# SLAMStruderBrd.net
KiCad netlist of a schematic drawn in EAGLE
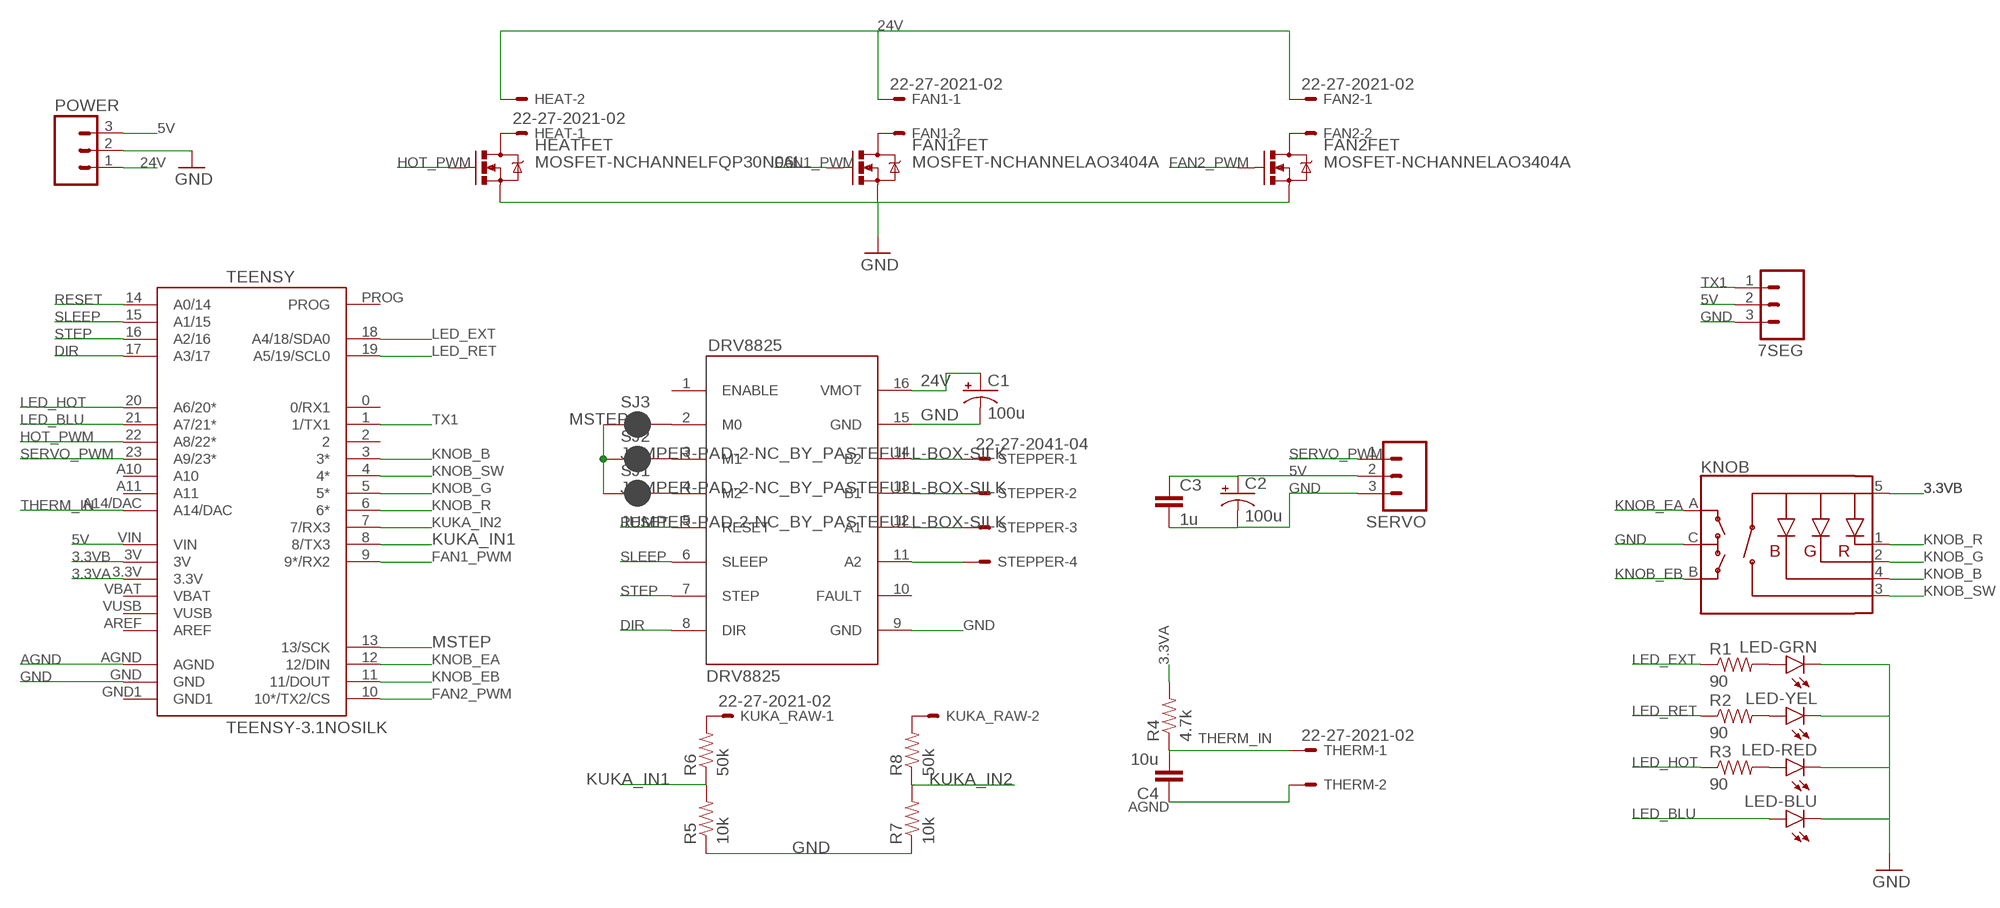
[diagram p0: schematic, sheet 1]

(export (version "E")
  (design (tool "Eeschema 10.0.6"))
  (components
    (comp (ref "7SEG")
      (value "M031X03_NO_SILK")
      (footprint "eagle-import:1X03_NO_SILK")
      (libsource (lib "eagle-import") (part "M031X03_NO_SILK"))
    )
    (comp (ref "C1")
      (value "100u")
      (footprint "eagle-import:PANASONIC_E")
      (libsource (lib "eagle-import") (part "CAP_POLE"))
    )
    (comp (ref "C2")
      (value "100u")
      (footprint "eagle-import:PANASONIC_E")
      (libsource (lib "eagle-import") (part "CAP_POLE"))
    )
    (comp (ref "C3")
      (value "1u")
      (footprint "eagle-import:0805")
      (libsource (lib "eagle-import") (part "CAP0805"))
    )
    (comp (ref "C4")
      (value "10u")
      (footprint "eagle-import:0805")
      (libsource (lib "eagle-import") (part "CAP0805"))
    )
    (comp (ref "DRV8825")
      (value "DRV8825")
      (footprint "eagle-import:STEPPER_DRIVER")
      (libsource (lib "eagle-import") (part "DRV8825"))
    )
    (comp (ref "FAN1")
      (value "22-27-2021-02")
      (footprint "eagle-import:6410-02")
      (libsource (lib "eagle-import") (part "22-?-0227-2021"))
    )
    (comp (ref "FAN1FET")
      (value "MOSFET-NCHANNELAO3404A")
      (footprint "eagle-import:SOT23-3")
      (libsource (lib "eagle-import") (part "MOSFET-NCHANNELAO3404A"))
    )
    (comp (ref "FAN2")
      (value "22-27-2021-02")
      (footprint "eagle-import:6410-02")
      (libsource (lib "eagle-import") (part "22-?-0227-2021"))
    )
    (comp (ref "FAN2FET")
      (value "MOSFET-NCHANNELAO3404A")
      (footprint "eagle-import:SOT23-3")
      (libsource (lib "eagle-import") (part "MOSFET-NCHANNELAO3404A"))
    )
    (comp (ref "HEAT")
      (value "22-27-2021-02")
      (footprint "eagle-import:6410-02")
      (libsource (lib "eagle-import") (part "22-?-0227-2021"))
    )
    (comp (ref "HEATFET")
      (value "MOSFET-NCHANNELFQP30N06L")
      (footprint "eagle-import:TO220V")
      (libsource (lib "eagle-import") (part "MOSFET-NCHANNELFQP30N06L"))
    )
    (comp (ref "KNOB")
      (value "ENCODER_RGB_CA")
      (footprint "eagle-import:ENCODER_LED_3")
      (libsource (lib "eagle-import") (part "ENCODER_RGB_CA"))
    )
    (comp (ref "KUKA_RAW")
      (value "22-27-2021-02")
      (footprint "eagle-import:6410-02")
      (libsource (lib "eagle-import") (part "22-?-0227-2021"))
    )
    (comp (ref "LED-BLU")
      (value "LED5MM")
      (footprint "eagle-import:LED5MM")
      (libsource (lib "eagle-import") (part "LED5MM"))
    )
    (comp (ref "LED-GRN")
      (value "LED5MM")
      (footprint "eagle-import:LED5MM")
      (libsource (lib "eagle-import") (part "LED5MM"))
    )
    (comp (ref "LED-RED")
      (value "LED5MM")
      (footprint "eagle-import:LED5MM")
      (libsource (lib "eagle-import") (part "LED5MM"))
    )
    (comp (ref "LED-YEL")
      (value "LED5MM")
      (footprint "eagle-import:LED5MM")
      (libsource (lib "eagle-import") (part "LED5MM"))
    )
    (comp (ref "POWER")
      (value "M03SCREW")
      (footprint "eagle-import:SCREWTERMINAL-3.5MM-3")
      (libsource (lib "eagle-import") (part "M03SCREW"))
    )
    (comp (ref "R1")
      (value "90")
      (footprint "eagle-import:0805")
      (libsource (lib "eagle-import") (part "RESISTOR0805-RES"))
    )
    (comp (ref "R2")
      (value "90")
      (footprint "eagle-import:0805")
      (libsource (lib "eagle-import") (part "RESISTOR0805-RES"))
    )
    (comp (ref "R3")
      (value "90")
      (footprint "eagle-import:0805")
      (libsource (lib "eagle-import") (part "RESISTOR0805-RES"))
    )
    (comp (ref "R4")
      (value "4.7k")
      (footprint "eagle-import:0805")
      (libsource (lib "eagle-import") (part "RESISTOR0805-RES"))
    )
    (comp (ref "R5")
      (value "10k")
      (footprint "eagle-import:0805")
      (libsource (lib "eagle-import") (part "RESISTOR0805-RES"))
    )
    (comp (ref "R6")
      (value "50k")
      (footprint "eagle-import:0805")
      (libsource (lib "eagle-import") (part "RESISTOR0805-RES"))
    )
    (comp (ref "R7")
      (value "10k")
      (footprint "eagle-import:0805")
      (libsource (lib "eagle-import") (part "RESISTOR0805-RES"))
    )
    (comp (ref "R8")
      (value "50k")
      (footprint "eagle-import:0805")
      (libsource (lib "eagle-import") (part "RESISTOR0805-RES"))
    )
    (comp (ref "SERVO")
      (value "M03PTH")
      (footprint "eagle-import:1X03")
      (libsource (lib "eagle-import") (part "M03PTH"))
    )
    (comp (ref "SJ1")
      (value "JUMPER-PAD-2-NC_BY_PASTEFULL-BOX-SILK")
      (footprint "eagle-import:PAD-JUMPER-2-NC_BY_PASTE_YES_SILK_FULL_BOX")
      (libsource (lib "eagle-import") (part "JUMPER-PAD-2-NC_BY_PASTEFULL-BOX-SILK"))
    )
    (comp (ref "SJ2")
      (value "JUMPER-PAD-2-NC_BY_PASTEFULL-BOX-SILK")
      (footprint "eagle-import:PAD-JUMPER-2-NC_BY_PASTE_YES_SILK_FULL_BOX")
      (libsource (lib "eagle-import") (part "JUMPER-PAD-2-NC_BY_PASTEFULL-BOX-SILK"))
    )
    (comp (ref "SJ3")
      (value "JUMPER-PAD-2-NC_BY_PASTEFULL-BOX-SILK")
      (footprint "eagle-import:PAD-JUMPER-2-NC_BY_PASTE_YES_SILK_FULL_BOX")
      (libsource (lib "eagle-import") (part "JUMPER-PAD-2-NC_BY_PASTEFULL-BOX-SILK"))
    )
    (comp (ref "STEPPER")
      (value "22-27-2041-04")
      (footprint "eagle-import:6410-04")
      (libsource (lib "eagle-import") (part "22-?-0427-2041"))
    )
    (comp (ref "TEENSY")
      (value "TEENSY-3.1NOSILK")
      (footprint "eagle-import:TEENSY-3.1_NOSILK")
      (libsource (lib "eagle-import") (part "TEENSY-3.1NOSILK"))
    )
    (comp (ref "THERM")
      (value "22-27-2021-02")
      (footprint "eagle-import:6410-02")
      (libsource (lib "eagle-import") (part "22-?-0227-2021"))
    )
  )
  (nets
    (net (code "1") (name "/3.3VA") (class "Default")
      (node (ref "R4") (pin "2") (pinfunction "2_2") (pintype "passive"))
      (node (ref "TEENSY") (pin "3.3V") (pinfunction "3.3V_3.3V") (pintype "bidirectional"))
    )
    (net (code "2") (name "/3.3VB") (class "Default")
      (node (ref "KNOB") (pin "5") (pinfunction "+_5") (pintype "passive"))
      (node (ref "TEENSY") (pin "3V") (pinfunction "3V_3V") (pintype "bidirectional"))
    )
    (net (code "3") (name "/5V") (class "Default")
      (node (ref "7SEG") (pin "2") (pinfunction "2_2") (pintype "passive"))
      (node (ref "C2") (pin "+") (pinfunction "+_+") (pintype "passive"))
      (node (ref "C3") (pin "1") (pinfunction "1_1") (pintype "passive"))
      (node (ref "POWER") (pin "3") (pinfunction "3_3") (pintype "passive"))
      (node (ref "SERVO") (pin "2") (pinfunction "2_2") (pintype "passive"))
      (node (ref "TEENSY") (pin "VIN") (pinfunction "VIN_VIN") (pintype "bidirectional"))
    )
    (net (code "4") (name "/24V") (class "Default")
      (node (ref "C1") (pin "+") (pinfunction "+_+") (pintype "passive"))
      (node (ref "DRV8825") (pin "16") (pinfunction "VMOT_16") (pintype "power_in"))
      (node (ref "FAN1") (pin "1") (pinfunction "S_1") (pintype "passive"))
      (node (ref "FAN2") (pin "1") (pinfunction "S_1") (pintype "passive"))
      (node (ref "HEAT") (pin "2") (pinfunction "S_2") (pintype "passive"))
      (node (ref "POWER") (pin "1") (pinfunction "1_1") (pintype "passive"))
    )
    (net (code "5") (name "/AGND") (class "Default")
      (node (ref "C4") (pin "1") (pinfunction "1_1") (pintype "passive"))
      (node (ref "TEENSY") (pin "AGND") (pinfunction "AGND_AGND") (pintype "bidirectional"))
      (node (ref "THERM") (pin "2") (pinfunction "S_2") (pintype "passive"))
    )
    (net (code "6") (name "/DIR") (class "Default")
      (node (ref "DRV8825") (pin "8") (pinfunction "DIR_8") (pintype "bidirectional"))
      (node (ref "TEENSY") (pin "17") (pinfunction "A3/17_17") (pintype "bidirectional"))
    )
    (net (code "7") (name "/FAN1_PWM") (class "Default")
      (node (ref "FAN1FET") (pin "1") (pinfunction "G_1") (pintype "passive"))
      (node (ref "TEENSY") (pin "9") (pinfunction "9*/RX2_9") (pintype "bidirectional"))
    )
    (net (code "8") (name "/FAN2_PWM") (class "Default")
      (node (ref "FAN2FET") (pin "1") (pinfunction "G_1") (pintype "passive"))
      (node (ref "TEENSY") (pin "10") (pinfunction "10*/TX2/CS_10") (pintype "bidirectional"))
    )
    (net (code "9") (name "/HOT_PWM") (class "Default")
      (node (ref "HEATFET") (pin "1") (pinfunction "G_1") (pintype "passive"))
      (node (ref "TEENSY") (pin "22") (pinfunction "A8/22*_22") (pintype "bidirectional"))
    )
    (net (code "10") (name "/KNOB_B") (class "Default")
      (node (ref "KNOB") (pin "4") (pinfunction "-B_4") (pintype "passive"))
      (node (ref "TEENSY") (pin "3") (pinfunction "3*_3") (pintype "bidirectional"))
    )
    (net (code "11") (name "/KNOB_EA") (class "Default")
      (node (ref "KNOB") (pin "A") (pinfunction "A_A") (pintype "bidirectional"))
      (node (ref "TEENSY") (pin "12") (pinfunction "12/DIN_12") (pintype "bidirectional"))
    )
    (net (code "12") (name "/KNOB_EB") (class "Default")
      (node (ref "KNOB") (pin "B") (pinfunction "B_B") (pintype "bidirectional"))
      (node (ref "TEENSY") (pin "11") (pinfunction "11/DOUT_11") (pintype "bidirectional"))
    )
    (net (code "13") (name "/KNOB_G") (class "Default")
      (node (ref "KNOB") (pin "2") (pinfunction "-G_2") (pintype "passive"))
      (node (ref "TEENSY") (pin "5") (pinfunction "5*_5") (pintype "bidirectional"))
    )
    (net (code "14") (name "/KNOB_R") (class "Default")
      (node (ref "KNOB") (pin "1") (pinfunction "-R_1") (pintype "passive"))
      (node (ref "TEENSY") (pin "6") (pinfunction "6*_6") (pintype "bidirectional"))
    )
    (net (code "15") (name "/KNOB_SW") (class "Default")
      (node (ref "KNOB") (pin "3") (pinfunction "SW_3") (pintype "passive"))
      (node (ref "TEENSY") (pin "4") (pinfunction "4*_4") (pintype "bidirectional"))
    )
    (net (code "16") (name "/KUKA_IN1") (class "Default")
      (node (ref "R5") (pin "2") (pinfunction "2_2") (pintype "passive"))
      (node (ref "R6") (pin "1") (pinfunction "1_1") (pintype "passive"))
      (node (ref "TEENSY") (pin "8") (pinfunction "8/TX3_8") (pintype "bidirectional"))
    )
    (net (code "17") (name "/KUKA_IN2") (class "Default")
      (node (ref "R7") (pin "2") (pinfunction "2_2") (pintype "passive"))
      (node (ref "R8") (pin "1") (pinfunction "1_1") (pintype "passive"))
      (node (ref "TEENSY") (pin "7") (pinfunction "7/RX3_7") (pintype "bidirectional"))
    )
    (net (code "18") (name "/LED_BLU") (class "Default")
      (node (ref "LED-BLU") (pin "A") (pinfunction "A_A") (pintype "passive"))
      (node (ref "TEENSY") (pin "21") (pinfunction "A7/21*_21") (pintype "bidirectional"))
    )
    (net (code "19") (name "/LED_EXT") (class "Default")
      (node (ref "R1") (pin "1") (pinfunction "1_1") (pintype "passive"))
      (node (ref "TEENSY") (pin "18") (pinfunction "A4/18/SDA0_18") (pintype "bidirectional"))
    )
    (net (code "20") (name "/LED_HOT") (class "Default")
      (node (ref "R3") (pin "1") (pinfunction "1_1") (pintype "passive"))
      (node (ref "TEENSY") (pin "20") (pinfunction "A6/20*_20") (pintype "bidirectional"))
    )
    (net (code "21") (name "/LED_RET") (class "Default")
      (node (ref "R2") (pin "1") (pinfunction "1_1") (pintype "passive"))
      (node (ref "TEENSY") (pin "19") (pinfunction "A5/19/SCL0_19") (pintype "bidirectional"))
    )
    (net (code "22") (name "/MSTEP") (class "Default")
      (node (ref "SJ1") (pin "1") (pinfunction "1_1") (pintype "passive"))
      (node (ref "SJ2") (pin "1") (pinfunction "1_1") (pintype "passive"))
      (node (ref "SJ3") (pin "1") (pinfunction "1_1") (pintype "passive"))
      (node (ref "TEENSY") (pin "13") (pinfunction "13/SCK_13") (pintype "bidirectional"))
    )
    (net (code "23") (name "/RESET") (class "Default")
      (node (ref "DRV8825") (pin "5") (pinfunction "RESET_5") (pintype "bidirectional"))
      (node (ref "TEENSY") (pin "14") (pinfunction "A0/14_14") (pintype "bidirectional"))
    )
    (net (code "24") (name "/SERVO_PWM") (class "Default")
      (node (ref "SERVO") (pin "1") (pinfunction "1_1") (pintype "passive"))
      (node (ref "TEENSY") (pin "23") (pinfunction "A9/23*_23") (pintype "bidirectional"))
    )
    (net (code "25") (name "/SLEEP") (class "Default")
      (node (ref "DRV8825") (pin "6") (pinfunction "SLEEP_6") (pintype "input"))
      (node (ref "TEENSY") (pin "15") (pinfunction "A1/15_15") (pintype "bidirectional"))
    )
    (net (code "26") (name "/STEP") (class "Default")
      (node (ref "DRV8825") (pin "7") (pinfunction "STEP_7") (pintype "input"))
      (node (ref "TEENSY") (pin "16") (pinfunction "A2/16_16") (pintype "bidirectional"))
    )
    (net (code "27") (name "/THERM_IN") (class "Default")
      (node (ref "C4") (pin "2") (pinfunction "2_2") (pintype "passive"))
      (node (ref "R4") (pin "1") (pinfunction "1_1") (pintype "passive"))
      (node (ref "TEENSY") (pin "A14/DAC") (pinfunction "A14/DAC_A14/DAC") (pintype "bidirectional"))
      (node (ref "THERM") (pin "1") (pinfunction "S_1") (pintype "passive"))
    )
    (net (code "28") (name "/TX1") (class "Default")
      (node (ref "7SEG") (pin "1") (pinfunction "1_1") (pintype "passive"))
      (node (ref "TEENSY") (pin "1") (pinfunction "1/TX1_1") (pintype "bidirectional"))
    )
    (net (code "29") (name "GND") (class "Default")
      (node (ref "7SEG") (pin "3") (pinfunction "3_3") (pintype "passive"))
      (node (ref "C1") (pin "-") (pinfunction "-_-") (pintype "passive"))
      (node (ref "C2") (pin "-") (pinfunction "-_-") (pintype "passive"))
      (node (ref "C3") (pin "2") (pinfunction "2_2") (pintype "passive"))
      (node (ref "DRV8825") (pin "15") (pinfunction "GND_15") (pintype "power_in"))
      (node (ref "DRV8825") (pin "9") (pinfunction "GND_9") (pintype "bidirectional"))
      (node (ref "FAN1FET") (pin "2") (pinfunction "S_2") (pintype "passive"))
      (node (ref "FAN2FET") (pin "2") (pinfunction "S_2") (pintype "passive"))
      (node (ref "HEATFET") (pin "3") (pinfunction "S_3") (pintype "passive"))
      (node (ref "KNOB") (pin "C") (pinfunction "C_C") (pintype "bidirectional"))
      (node (ref "LED-BLU") (pin "K") (pinfunction "C_K") (pintype "passive"))
      (node (ref "LED-GRN") (pin "K") (pinfunction "C_K") (pintype "passive"))
      (node (ref "LED-RED") (pin "K") (pinfunction "C_K") (pintype "passive"))
      (node (ref "LED-YEL") (pin "K") (pinfunction "C_K") (pintype "passive"))
      (node (ref "POWER") (pin "2") (pinfunction "2_2") (pintype "passive"))
      (node (ref "R5") (pin "1") (pinfunction "1_1") (pintype "passive"))
      (node (ref "R7") (pin "1") (pinfunction "1_1") (pintype "passive"))
      (node (ref "SERVO") (pin "3") (pinfunction "3_3") (pintype "passive"))
      (node (ref "TEENSY") (pin "GND") (pinfunction "GND_GND") (pintype "bidirectional"))
    )
    (net (code "30") (name "Net-(DRV8825-A1)") (class "Default")
      (node (ref "DRV8825") (pin "12") (pinfunction "A1_12") (pintype "output"))
      (node (ref "STEPPER") (pin "3") (pinfunction "S_3") (pintype "passive"))
    )
    (net (code "31") (name "Net-(DRV8825-A2)") (class "Default")
      (node (ref "DRV8825") (pin "11") (pinfunction "A2_11") (pintype "output"))
      (node (ref "STEPPER") (pin "4") (pinfunction "S_4") (pintype "passive"))
    )
    (net (code "32") (name "Net-(DRV8825-B1)") (class "Default")
      (node (ref "DRV8825") (pin "13") (pinfunction "B1_13") (pintype "output"))
      (node (ref "STEPPER") (pin "2") (pinfunction "S_2") (pintype "passive"))
    )
    (net (code "33") (name "Net-(DRV8825-B2)") (class "Default")
      (node (ref "DRV8825") (pin "14") (pinfunction "B2_14") (pintype "output"))
      (node (ref "STEPPER") (pin "1") (pinfunction "S_1") (pintype "passive"))
    )
    (net (code "34") (name "Net-(DRV8825-M0)") (class "Default")
      (node (ref "DRV8825") (pin "2") (pinfunction "M0_2") (pintype "input"))
      (node (ref "SJ3") (pin "2") (pinfunction "2_2") (pintype "passive"))
    )
    (net (code "35") (name "Net-(DRV8825-M1)") (class "Default")
      (node (ref "DRV8825") (pin "3") (pinfunction "M1_3") (pintype "input"))
      (node (ref "SJ2") (pin "2") (pinfunction "2_2") (pintype "passive"))
    )
    (net (code "36") (name "Net-(DRV8825-M2)") (class "Default")
      (node (ref "DRV8825") (pin "4") (pinfunction "M2_4") (pintype "input"))
      (node (ref "SJ1") (pin "2") (pinfunction "2_2") (pintype "passive"))
    )
    (net (code "37") (name "Net-(FAN1B-S)") (class "Default")
      (node (ref "FAN1") (pin "2") (pinfunction "S_2") (pintype "passive"))
      (node (ref "FAN1FET") (pin "3") (pinfunction "D_3") (pintype "passive"))
    )
    (net (code "38") (name "Net-(FAN2B-S)") (class "Default")
      (node (ref "FAN2") (pin "2") (pinfunction "S_2") (pintype "passive"))
      (node (ref "FAN2FET") (pin "3") (pinfunction "D_3") (pintype "passive"))
    )
    (net (code "39") (name "Net-(HEATA-S)") (class "Default")
      (node (ref "HEAT") (pin "1") (pinfunction "S_1") (pintype "passive"))
      (node (ref "HEATFET") (pin "2") (pinfunction "D_2") (pintype "passive"))
    )
    (net (code "40") (name "Net-(KUKA_RAWA-S)") (class "Default")
      (node (ref "KUKA_RAW") (pin "1") (pinfunction "S_1") (pintype "passive"))
      (node (ref "R6") (pin "2") (pinfunction "2_2") (pintype "passive"))
    )
    (net (code "41") (name "Net-(KUKA_RAWB-S)") (class "Default")
      (node (ref "KUKA_RAW") (pin "2") (pinfunction "S_2") (pintype "passive"))
      (node (ref "R8") (pin "2") (pinfunction "2_2") (pintype "passive"))
    )
    (net (code "42") (name "Net-(LED-GRN-PadA)") (class "Default")
      (node (ref "LED-GRN") (pin "A") (pinfunction "A_A") (pintype "passive"))
      (node (ref "R1") (pin "2") (pinfunction "2_2") (pintype "passive"))
    )
    (net (code "43") (name "Net-(LED-RED-PadA)") (class "Default")
      (node (ref "LED-RED") (pin "A") (pinfunction "A_A") (pintype "passive"))
      (node (ref "R3") (pin "2") (pinfunction "2_2") (pintype "passive"))
    )
    (net (code "44") (name "Net-(LED-YEL-PadA)") (class "Default")
      (node (ref "LED-YEL") (pin "A") (pinfunction "A_A") (pintype "passive"))
      (node (ref "R2") (pin "2") (pinfunction "2_2") (pintype "passive"))
    )
    (net (code "45") (name "unconnected-(DRV8825-ENABLE-Pad1)") (class "Default")
      (node (ref "DRV8825") (pin "1") (pinfunction "ENABLE_1") (pintype "input"))
    )
    (net (code "46") (name "unconnected-(DRV8825-FAULT-Pad10)") (class "Default")
      (node (ref "DRV8825") (pin "10") (pinfunction "FAULT_10") (pintype "output"))
    )
    (net (code "47") (name "unconnected-(TEENSY-0{slash}RX1-Pad0)") (class "Default")
      (node (ref "TEENSY") (pin "0") (pinfunction "0/RX1_0") (pintype "bidirectional"))
    )
    (net (code "48") (name "unconnected-(TEENSY-Pad2)") (class "Default")
      (node (ref "TEENSY") (pin "2") (pinfunction "2_2") (pintype "bidirectional"))
    )
    (net (code "49") (name "unconnected-(TEENSY-PadA10)") (class "Default")
      (node (ref "TEENSY") (pin "A10") (pinfunction "A10_A10") (pintype "bidirectional"))
    )
    (net (code "50") (name "unconnected-(TEENSY-PadA11)") (class "Default")
      (node (ref "TEENSY") (pin "A11") (pinfunction "A11_A11") (pintype "bidirectional"))
    )
    (net (code "51") (name "unconnected-(TEENSY-PadAREF)") (class "Default")
      (node (ref "TEENSY") (pin "AREF") (pinfunction "AREF_AREF") (pintype "bidirectional"))
    )
    (net (code "52") (name "unconnected-(TEENSY-PadGND1)") (class "Default")
      (node (ref "TEENSY") (pin "GND1") (pinfunction "GND1_GND1") (pintype "bidirectional"))
    )
    (net (code "53") (name "unconnected-(TEENSY-PadPROG)") (class "Default")
      (node (ref "TEENSY") (pin "PROG") (pinfunction "PROG_PROG") (pintype "bidirectional"))
    )
    (net (code "54") (name "unconnected-(TEENSY-PadVBAT)") (class "Default")
      (node (ref "TEENSY") (pin "VBAT") (pinfunction "VBAT_VBAT") (pintype "bidirectional"))
    )
    (net (code "55") (name "unconnected-(TEENSY-PadVUSB)") (class "Default")
      (node (ref "TEENSY") (pin "VUSB") (pinfunction "VUSB_VUSB") (pintype "bidirectional"))
    )
  )
)
